# PD_Controller.net
KiCad netlist of a schematic drawn in EAGLE
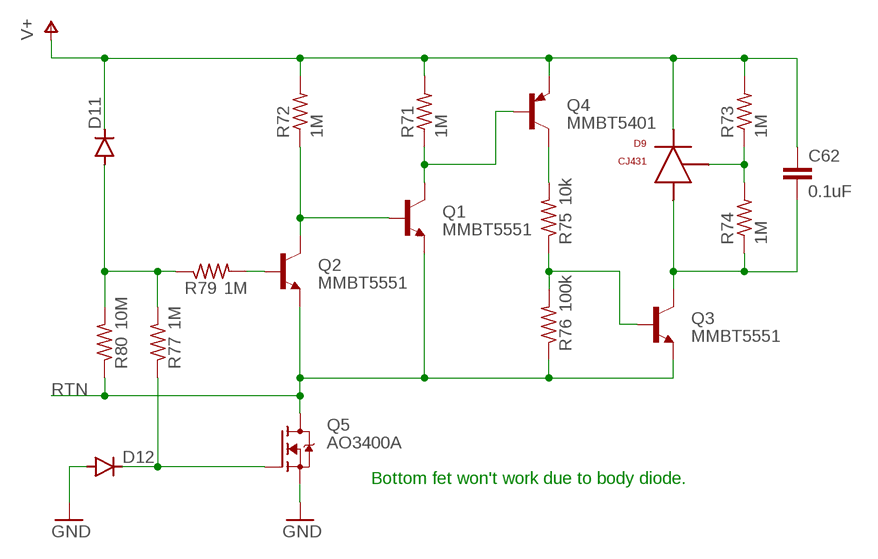
[diagram p0: schematic, sheet 1]

(export (version "E")
  (design (tool "Eeschema 10.0.6"))
  (components
    (comp (ref "C62")
      (value "0.1uF")
      (footprint "eagle-import:0402_INDUCTOR")
      (libsource (lib "eagle-import") (part "0402_CAPACITOR"))
    )
    (comp (ref "D9")
      (value "CJ431")
      (footprint "eagle-import:SOT23-3_CENTERED")
      (libsource (lib "eagle-import") (part "CJ431"))
    )
    (comp (ref "D11")
      (value "DIODE-MINIMELF")
      (footprint "eagle-import:MINIMELF")
      (libsource (lib "eagle-import") (part "DIODE-MINIMELF"))
    )
    (comp (ref "D12")
      (value "DIODE-MINIMELF")
      (footprint "eagle-import:MINIMELF")
      (libsource (lib "eagle-import") (part "DIODE-MINIMELF"))
    )
    (comp (ref "Q1")
      (value "MMBT5551")
      (footprint "eagle-import:SOT23-3_CENTERED")
      (libsource (lib "eagle-import") (part "MMBT3904-TPCENTERED"))
    )
    (comp (ref "Q2")
      (value "MMBT5551")
      (footprint "eagle-import:SOT23-3_CENTERED")
      (libsource (lib "eagle-import") (part "MMBT3904-TPCENTERED"))
    )
    (comp (ref "Q3")
      (value "MMBT5551")
      (footprint "eagle-import:SOT23-3_CENTERED")
      (libsource (lib "eagle-import") (part "MMBT3904-TPCENTERED"))
    )
    (comp (ref "Q4")
      (value "MMBT5401")
      (footprint "eagle-import:SOT23-3_CENTERED")
      (libsource (lib "eagle-import") (part "MMBT3906-7-FCENTERED"))
    )
    (comp (ref "Q5")
      (value "AO3400A")
      (footprint "eagle-import:SOT23-3_CENTERED")
      (libsource (lib "eagle-import") (part "AO3400A"))
    )
    (comp (ref "R71")
      (value "1M")
      (footprint "eagle-import:0603")
      (libsource (lib "eagle-import") (part "0603_RESISTOR"))
    )
    (comp (ref "R72")
      (value "1M")
      (footprint "eagle-import:0603")
      (libsource (lib "eagle-import") (part "0603_RESISTOR"))
    )
    (comp (ref "R73")
      (value "1M")
      (footprint "eagle-import:0603")
      (libsource (lib "eagle-import") (part "0603_RESISTOR"))
    )
    (comp (ref "R74")
      (value "1M")
      (footprint "eagle-import:0603")
      (libsource (lib "eagle-import") (part "0603_RESISTOR"))
    )
    (comp (ref "R75")
      (value "10k")
      (footprint "eagle-import:R0402")
      (libsource (lib "eagle-import") (part "0402_RESISTOR"))
    )
    (comp (ref "R76")
      (value "100k")
      (footprint "eagle-import:R0402")
      (libsource (lib "eagle-import") (part "0402_RESISTOR"))
    )
    (comp (ref "R77")
      (value "1M")
      (footprint "eagle-import:R0402")
      (libsource (lib "eagle-import") (part "0402_RESISTOR"))
    )
    (comp (ref "R79")
      (value "1M")
      (footprint "eagle-import:R0402")
      (libsource (lib "eagle-import") (part "0402_RESISTOR"))
    )
    (comp (ref "R80")
      (value "10M")
      (footprint "eagle-import:R0402")
      (libsource (lib "eagle-import") (part "0402_RESISTOR"))
    )
  )
  (nets
    (net (code "1") (name "/RTN") (class "Default")
      (node (ref "Q1") (pin "2") (pinfunction "E_2") (pintype "passive"))
      (node (ref "Q2") (pin "2") (pinfunction "E_2") (pintype "passive"))
      (node (ref "Q3") (pin "2") (pinfunction "E_2") (pintype "passive"))
      (node (ref "Q5") (pin "3") (pinfunction "D_3") (pintype "passive"))
      (node (ref "R76") (pin "1") (pinfunction "1_1") (pintype "passive"))
      (node (ref "R80") (pin "1") (pinfunction "1_1") (pintype "passive"))
    )
    (net (code "2") (name "GND") (class "Default")
      (node (ref "D12") (pin "A") (pinfunction "A_A") (pintype "passive"))
      (node (ref "Q5") (pin "2") (pinfunction "S_2") (pintype "passive"))
    )
    (net (code "3") (name "Net-(C62-2)") (class "Default")
      (node (ref "C62") (pin "P$2") (pinfunction "2_P$2") (pintype "passive"))
      (node (ref "D9") (pin "3") (pinfunction "A_3") (pintype "bidirectional"))
      (node (ref "Q3") (pin "3") (pinfunction "C_3") (pintype "passive"))
      (node (ref "R74") (pin "1") (pinfunction "1_1") (pintype "passive"))
    )
    (net (code "4") (name "Net-(D9-REF)") (class "Default")
      (node (ref "D9") (pin "1") (pinfunction "REF_1") (pintype "bidirectional"))
      (node (ref "R73") (pin "1") (pinfunction "1_1") (pintype "passive"))
      (node (ref "R74") (pin "2") (pinfunction "2_2") (pintype "passive"))
    )
    (net (code "5") (name "Net-(D11-PadA)") (class "Default")
      (node (ref "D11") (pin "A") (pinfunction "A_A") (pintype "passive"))
      (node (ref "R77") (pin "2") (pinfunction "2_2") (pintype "passive"))
      (node (ref "R79") (pin "1") (pinfunction "1_1") (pintype "passive"))
      (node (ref "R80") (pin "2") (pinfunction "2_2") (pintype "passive"))
    )
    (net (code "6") (name "Net-(Q1-B)") (class "Default")
      (node (ref "Q1") (pin "1") (pinfunction "B_1") (pintype "passive"))
      (node (ref "Q2") (pin "3") (pinfunction "C_3") (pintype "passive"))
      (node (ref "R72") (pin "1") (pinfunction "1_1") (pintype "passive"))
    )
    (net (code "7") (name "Net-(Q1-C)") (class "Default")
      (node (ref "Q1") (pin "3") (pinfunction "C_3") (pintype "passive"))
      (node (ref "Q4") (pin "1") (pinfunction "B_1") (pintype "passive"))
      (node (ref "R71") (pin "1") (pinfunction "1_1") (pintype "passive"))
    )
    (net (code "8") (name "Net-(Q2-B)") (class "Default")
      (node (ref "Q2") (pin "1") (pinfunction "B_1") (pintype "passive"))
      (node (ref "R79") (pin "2") (pinfunction "2_2") (pintype "passive"))
    )
    (net (code "9") (name "Net-(Q3-B)") (class "Default")
      (node (ref "Q3") (pin "1") (pinfunction "B_1") (pintype "passive"))
      (node (ref "R75") (pin "1") (pinfunction "1_1") (pintype "passive"))
      (node (ref "R76") (pin "2") (pinfunction "2_2") (pintype "passive"))
    )
    (net (code "10") (name "Net-(Q4-C)") (class "Default")
      (node (ref "Q4") (pin "3") (pinfunction "C_3") (pintype "passive"))
      (node (ref "R75") (pin "2") (pinfunction "2_2") (pintype "passive"))
    )
    (net (code "11") (name "Net-(Q5-G)") (class "Default")
      (node (ref "D12") (pin "C") (pinfunction "C_C") (pintype "passive"))
      (node (ref "Q5") (pin "1") (pinfunction "G_1") (pintype "passive"))
      (node (ref "R77") (pin "1") (pinfunction "1_1") (pintype "passive"))
    )
    (net (code "12") (name "V+") (class "Default")
      (node (ref "C62") (pin "P$1") (pinfunction "1_P$1") (pintype "passive"))
      (node (ref "D11") (pin "C") (pinfunction "C_C") (pintype "passive"))
      (node (ref "D9") (pin "2") (pinfunction "K_2") (pintype "bidirectional"))
      (node (ref "Q4") (pin "2") (pinfunction "E_2") (pintype "passive"))
      (node (ref "R71") (pin "2") (pinfunction "2_2") (pintype "passive"))
      (node (ref "R72") (pin "2") (pinfunction "2_2") (pintype "passive"))
      (node (ref "R73") (pin "2") (pinfunction "2_2") (pintype "passive"))
    )
  )
)
